# 2_bucks_a_and_s.net
KiCad netlist of a schematic drawn in EAGLE
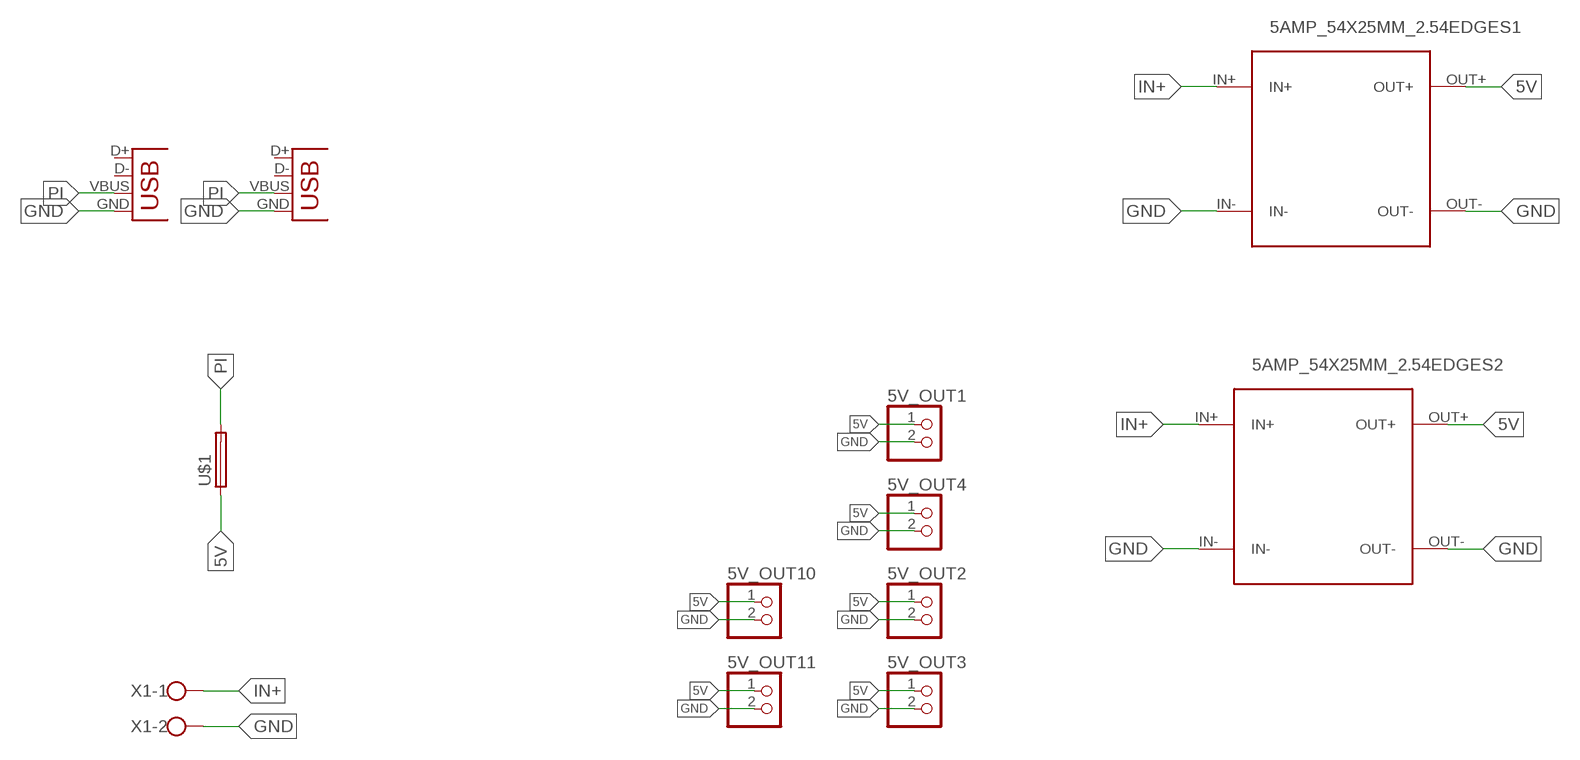
[diagram p0: schematic, sheet 1]

(export (version "E")
  (design (tool "Eeschema 10.0.6"))
  (components
    (comp (ref "5AMP_54X25MM_2.54EDGES1")
      (value "BUCKCONVERTER_5AMP_54X25MM")
      (footprint "eagle-import:BUCKCONVERTER_5AMP_54X25MM")
      (libsource (lib "eagle-import") (part "BUCKCONVERTER_5AMP_54X25MM"))
    )
    (comp (ref "5AMP_54X25MM_2.54EDGES2")
      (value "BUCKCONVERTER_5AMP_54X25MM")
      (footprint "eagle-import:BUCKCONVERTER_5AMP_54X25MM")
      (libsource (lib "eagle-import") (part "BUCKCONVERTER_5AMP_54X25MM"))
    )
    (comp (ref "5V_OUT1")
      (value "PINHD-2_DATA")
      (footprint "eagle-import:1X02_DATA")
      (libsource (lib "eagle-import") (part "PINHD-2_DATA"))
    )
    (comp (ref "5V_OUT2")
      (value "PINHD-2_DATA")
      (footprint "eagle-import:1X02_DATA")
      (libsource (lib "eagle-import") (part "PINHD-2_DATA"))
    )
    (comp (ref "5V_OUT3")
      (value "PINHD-2_DATA")
      (footprint "eagle-import:1X02_DATA")
      (libsource (lib "eagle-import") (part "PINHD-2_DATA"))
    )
    (comp (ref "5V_OUT4")
      (value "PINHD-2_DATA")
      (footprint "eagle-import:1X02_DATA")
      (libsource (lib "eagle-import") (part "PINHD-2_DATA"))
    )
    (comp (ref "5V_OUT10")
      (value "PINHD-2_DATA")
      (footprint "eagle-import:1X02_DATA")
      (libsource (lib "eagle-import") (part "PINHD-2_DATA"))
    )
    (comp (ref "5V_OUT11")
      (value "PINHD-2_DATA")
      (footprint "eagle-import:1X02_DATA")
      (libsource (lib "eagle-import") (part "PINHD-2_DATA"))
    )
    (comp (ref "U$1")
      (value "FUSE_HOLDER")
      (footprint "eagle-import:SH22,5A")
      (libsource (lib "eagle-import") (part "FUSE_HOLDER"))
    )
    (comp (ref "X1")
      (value "ROSTA.POWER")
      (footprint "eagle-import:W239-302")
      (libsource (lib "eagle-import") (part "ROSTA.POWER"))
    )
    (comp (ref "X2")
      (value "USB-A-H")
      (footprint "eagle-import:USB-A-H")
      (libsource (lib "eagle-import") (part "USB-A-H"))
    )
    (comp (ref "X4")
      (value "USB-A-H")
      (footprint "eagle-import:USB-A-H")
      (libsource (lib "eagle-import") (part "USB-A-H"))
    )
  )
  (nets
    (net (code "1") (name "5V") (class "Default")
      (node (ref "5AMP_54X25MM_2.54EDGES1") (pin "OUT+") (pinfunction "OUT+_OUT+") (pintype "bidirectional"))
      (node (ref "5AMP_54X25MM_2.54EDGES2") (pin "OUT+") (pinfunction "OUT+_OUT+") (pintype "bidirectional"))
      (node (ref "5V_OUT1") (pin "1") (pinfunction "1_1") (pintype "passive"))
      (node (ref "5V_OUT10") (pin "1") (pinfunction "1_1") (pintype "passive"))
      (node (ref "5V_OUT11") (pin "1") (pinfunction "1_1") (pintype "passive"))
      (node (ref "5V_OUT2") (pin "1") (pinfunction "1_1") (pintype "passive"))
      (node (ref "5V_OUT3") (pin "1") (pinfunction "1_1") (pintype "passive"))
      (node (ref "5V_OUT4") (pin "1") (pinfunction "1_1") (pintype "passive"))
      (node (ref "U$1") (pin "1") (pinfunction "1_1") (pintype "passive"))
    )
    (net (code "2") (name "GND") (class "Default")
      (node (ref "5AMP_54X25MM_2.54EDGES1") (pin "IN-") (pinfunction "IN-_IN-") (pintype "bidirectional"))
      (node (ref "5AMP_54X25MM_2.54EDGES1") (pin "OUT-") (pinfunction "OUT-_OUT-") (pintype "bidirectional"))
      (node (ref "5AMP_54X25MM_2.54EDGES2") (pin "IN-") (pinfunction "IN-_IN-") (pintype "bidirectional"))
      (node (ref "5AMP_54X25MM_2.54EDGES2") (pin "OUT-") (pinfunction "OUT-_OUT-") (pintype "bidirectional"))
      (node (ref "5V_OUT1") (pin "2") (pinfunction "2_2") (pintype "passive"))
      (node (ref "5V_OUT10") (pin "2") (pinfunction "2_2") (pintype "passive"))
      (node (ref "5V_OUT11") (pin "2") (pinfunction "2_2") (pintype "passive"))
      (node (ref "5V_OUT2") (pin "2") (pinfunction "2_2") (pintype "passive"))
      (node (ref "5V_OUT3") (pin "2") (pinfunction "2_2") (pintype "passive"))
      (node (ref "5V_OUT4") (pin "2") (pinfunction "2_2") (pintype "passive"))
      (node (ref "X1") (pin "2") (pinfunction "KL_2") (pintype "passive"))
      (node (ref "X2") (pin "GND") (pinfunction "GND_GND") (pintype "bidirectional"))
      (node (ref "X4") (pin "GND") (pinfunction "GND_GND") (pintype "bidirectional"))
    )
    (net (code "3") (name "IN+") (class "Default")
      (node (ref "5AMP_54X25MM_2.54EDGES1") (pin "IN+") (pinfunction "IN+_IN+") (pintype "bidirectional"))
      (node (ref "5AMP_54X25MM_2.54EDGES2") (pin "IN+") (pinfunction "IN+_IN+") (pintype "bidirectional"))
      (node (ref "X1") (pin "1") (pinfunction "KL_1") (pintype "passive"))
    )
    (net (code "4") (name "PI") (class "Default")
      (node (ref "U$1") (pin "2") (pinfunction "2_2") (pintype "passive"))
      (node (ref "X2") (pin "VBUS") (pinfunction "VBUS_VBUS") (pintype "bidirectional"))
      (node (ref "X4") (pin "VBUS") (pinfunction "VBUS_VBUS") (pintype "bidirectional"))
    )
    (net (code "5") (name "unconnected-(X2-PadD+)") (class "Default")
      (node (ref "X2") (pin "D+") (pinfunction "D+_D+") (pintype "bidirectional"))
    )
    (net (code "6") (name "unconnected-(X2-PadD-)") (class "Default")
      (node (ref "X2") (pin "D-") (pinfunction "D-_D-") (pintype "bidirectional"))
    )
    (net (code "7") (name "unconnected-(X4-PadD+)") (class "Default")
      (node (ref "X4") (pin "D+") (pinfunction "D+_D+") (pintype "bidirectional"))
    )
    (net (code "8") (name "unconnected-(X4-PadD-)") (class "Default")
      (node (ref "X4") (pin "D-") (pinfunction "D-_D-") (pintype "bidirectional"))
    )
  )
)
